# RTC.net
KiCad netlist of a schematic drawn in Altium Designer
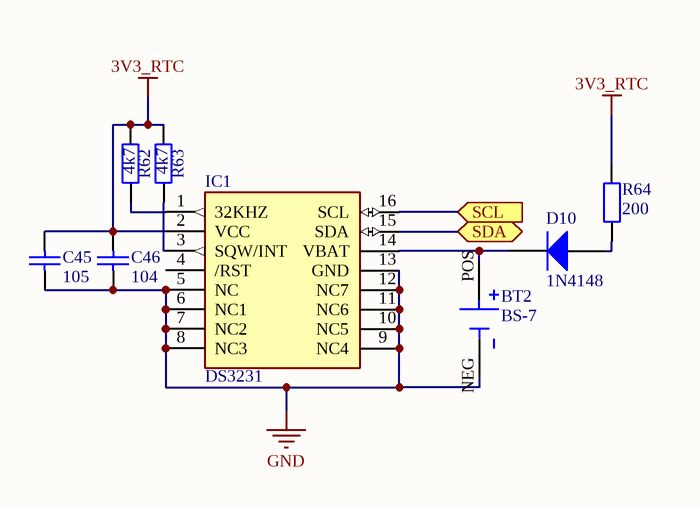
[diagram p0: RTC.SchDoc]

(export (version "E")
  (design (tool "Eeschema 10.0.6"))
  (components
    (comp (ref "BT2")
      (value "BS-7")
      (footprint "BAT_BS-7")
      (description "Battery Holder (Open) Coin, 20.0mm 1 Cell PC Pin")
      (fields (field (name "MF") "MPD (Memory") (field (name "DIGI-KEY_PART_NUMBER") "BS-7-ND"))
      (libsource (lib "CR_BATTERY") (part "BS-7"))
    )
    (comp (ref "C45") (value "105") (footprint "0603_Cap") (libsource (lib "CMN") (part "Ceramic Capacitor")))
    (comp (ref "C46") (value "104") (footprint "0603_Cap") (libsource (lib "CMN") (part "Ceramic Capacitor")))
    (comp (ref "D10") (value "1N4148") (footprint "SOD-323") (libsource (lib "CMN") (part "Diode")))
    (comp (ref "IC1")
      (value "DS3231")
      (footprint "SOIC-16")
      (description "Real Time Clock (RTC) IC Clock/Calendar - IÂ²C, 2-Wire Serial 8-SOIC (0.154, 3.90mm Width)")
      (fields (field (name "MF") "Maxim Integrated"))
      (libsource (lib "CMN") (part "DS3231"))
    )
    (comp (ref "R62") (value "4k7") (footprint "0603_Res") (libsource (lib "CMN") (part "Resistor")))
    (comp (ref "R63") (value "4k7") (footprint "0603_Res") (libsource (lib "CMN") (part "Resistor")))
    (comp (ref "R64") (value "200") (footprint "0603_Res") (libsource (lib "CMN") (part "Resistor")))
  )
  (nets
    (net (code "1") (name "/SCL") (class "Default")
      (node (ref "IC1") (pin "16") (pinfunction "SCL_16") (pintype "bidirectional"))
    )
    (net (code "2") (name "/SDA") (class "Default")
      (node (ref "IC1") (pin "15") (pinfunction "SDA_15") (pintype "bidirectional"))
    )
    (net (code "3") (name "3V3_RTC") (class "Default")
      (node (ref "C45") (pin "1") (pinfunction "1_1") (pintype "passive"))
      (node (ref "C46") (pin "1") (pinfunction "1_1") (pintype "passive"))
      (node (ref "IC1") (pin "2") (pinfunction "VCC_2") (pintype "power_in"))
      (node (ref "R62") (pin "2") (pinfunction "2_2") (pintype "passive"))
      (node (ref "R63") (pin "2") (pinfunction "2_2") (pintype "passive"))
      (node (ref "R64") (pin "1") (pinfunction "1_1") (pintype "passive"))
    )
    (net (code "4") (name "GND") (class "Default")
      (node (ref "BT2") (pin "NEG") (pinfunction "NEG_NEG") (pintype "passive"))
      (node (ref "C45") (pin "2") (pinfunction "2_2") (pintype "passive"))
      (node (ref "C46") (pin "2") (pinfunction "2_2") (pintype "passive"))
      (node (ref "IC1") (pin "10") (pinfunction "NC5_10") (pintype "passive"))
      (node (ref "IC1") (pin "11") (pinfunction "NC6_11") (pintype "passive"))
      (node (ref "IC1") (pin "12") (pinfunction "NC7_12") (pintype "passive"))
      (node (ref "IC1") (pin "13") (pinfunction "GND_13") (pintype "power_in"))
      (node (ref "IC1") (pin "5") (pinfunction "NC_5") (pintype "passive"))
      (node (ref "IC1") (pin "6") (pinfunction "NC1_6") (pintype "passive"))
      (node (ref "IC1") (pin "7") (pinfunction "NC2_7") (pintype "passive"))
      (node (ref "IC1") (pin "8") (pinfunction "NC3_8") (pintype "passive"))
      (node (ref "IC1") (pin "9") (pinfunction "NC4_9") (pintype "passive"))
    )
    (net (code "5") (name "Net-(D10-Pad2)") (class "Default")
      (node (ref "D10") (pin "2") (pinfunction "2_2") (pintype "passive"))
      (node (ref "R64") (pin "2") (pinfunction "2_2") (pintype "passive"))
    )
    (net (code "6") (name "Net-(IC1-32KHZ)") (class "Default")
      (node (ref "IC1") (pin "1") (pinfunction "32KHZ_1") (pintype "output"))
      (node (ref "R62") (pin "1") (pinfunction "1_1") (pintype "passive"))
    )
    (net (code "7") (name "Net-(IC1-SQW{slash}INT)") (class "Default")
      (node (ref "IC1") (pin "3") (pinfunction "SQW/INT_3") (pintype "output"))
      (node (ref "R63") (pin "1") (pinfunction "1_1") (pintype "passive"))
    )
    (net (code "8") (name "Net-(IC1-VBAT)") (class "Default")
      (node (ref "BT2") (pin "POS") (pinfunction "POS_POS") (pintype "passive"))
      (node (ref "D10") (pin "1") (pinfunction "1_1") (pintype "passive"))
      (node (ref "IC1") (pin "14") (pinfunction "VBAT_14") (pintype "power_in"))
    )
    (net (code "9") (name "unconnected-(IC1-{slash}RST-Pad4)") (class "Default")
      (node (ref "IC1") (pin "4") (pinfunction "/RST_4") (pintype "passive"))
    )
  )
)
